# STEVAL-ESLST25CB.net
KiCad netlist of a schematic drawn in Altium Designer
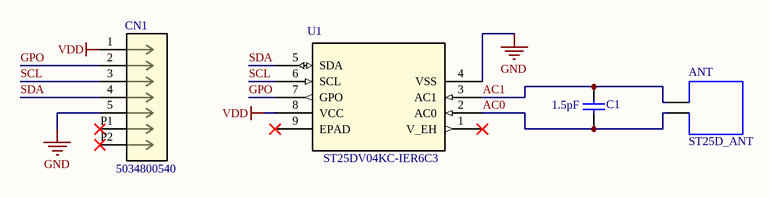
[diagram p0: STEVAL-ESLST25CB.SchDoc]

(export (version "E")
  (design (tool "Eeschema 10.0.6"))
  (components
    (comp (ref "ANT")
      (value "ST25D_ANT")
      (footprint "ESL_NFC_ANT")
      (description "ST25D antenna")
      (libsource (lib "STEVAL-ESLST25CB") (part "ST25D_ANT"))
    )
    (comp (ref "C1")
      (value "1.5pF")
      (footprint "C0402")
      (description "Multilayer Ceramic Capacitor, 1.5 pF, 50 V, ± 0.1pF, C0G (NP0), 0402 [1005 Metric]")
      (fields
        (field (name "MANUFACTURER") "Murata")
        (field (name "MANUFACTURER PART NUMBER") "GJM1555C1H1R5BB01D")
      )
      (libsource (lib "STEVAL-ESLST25CB") (part "Capacitor"))
    )
    (comp (ref "CN1")
      (value "5034800540")
      (footprint "CON_5034800540_MOL")
      (fields
        (field (name "MANUFACTURER") "Molex Connector Corporation")
        (field (name "COPYRIGHT") "Copyright (C) 2023 Ultra Librarian. All rights reserved.")
      )
      (libsource (lib "STEVAL-ESLST25CB") (part "5034800540_5_circuits"))
    )
    (comp (ref "U1")
      (value "ST25DV04KC-IER6C3")
      (footprint "UFDFPN8_STM")
      (description "NFC/RFID Tag and Transponder IC 13553kHz to 13567kHz 4Kbit 8-Pin UFDFPN T/R")
      (fields
        (field (name "MANUFACTURER_PART_NUMBER") "ST25DV04K-IER6C3")
        (field (name "MANUFACTURER") "STMicroelectronics")
        (field (name "COPYRIGHT") "Copyright (C) 2023 Ultra Librarian. All rights reserved.")
      )
      (libsource (lib "STEVAL-ESLST25CB") (part "ST25DV04K-IER6C3"))
    )
  )
  (nets
    (net (code "1") (name "/AC0") (class "Default")
      (node (ref "ANT") (pin "2") (pinfunction "2_2") (pintype "passive"))
      (node (ref "C1") (pin "2") (pinfunction "2_2") (pintype "passive"))
      (node (ref "U1") (pin "2") (pinfunction "AC0_2") (pintype "input"))
    )
    (net (code "2") (name "/AC1") (class "Default")
      (node (ref "ANT") (pin "1") (pinfunction "1_1") (pintype "passive"))
      (node (ref "C1") (pin "1") (pinfunction "1_1") (pintype "passive"))
      (node (ref "U1") (pin "3") (pinfunction "AC1_3") (pintype "input"))
    )
    (net (code "3") (name "/GPO") (class "Default")
      (node (ref "CN1") (pin "2") (pinfunction "2_2") (pintype "passive"))
      (node (ref "U1") (pin "7") (pinfunction "GPO_7") (pintype "output"))
    )
    (net (code "4") (name "/SCL") (class "Default")
      (node (ref "CN1") (pin "3") (pinfunction "3_3") (pintype "passive"))
      (node (ref "U1") (pin "6") (pinfunction "SCL_6") (pintype "input"))
    )
    (net (code "5") (name "/SDA") (class "Default")
      (node (ref "CN1") (pin "4") (pinfunction "4_4") (pintype "passive"))
      (node (ref "U1") (pin "5") (pinfunction "SDA_5") (pintype "bidirectional"))
    )
    (net (code "6") (name "GND") (class "Default")
      (node (ref "CN1") (pin "5") (pinfunction "5_5") (pintype "passive"))
      (node (ref "U1") (pin "4") (pinfunction "VSS_4") (pintype "power_in"))
    )
    (net (code "7") (name "VDD") (class "Default")
      (node (ref "CN1") (pin "1") (pinfunction "1_1") (pintype "passive"))
      (node (ref "U1") (pin "8") (pinfunction "VCC_8") (pintype "power_in"))
    )
    (net (code "8") (name "unconnected-(CN1-PadP1)") (class "Default")
      (node (ref "CN1") (pin "P1") (pinfunction "P1_P1") (pintype "passive+no_connect"))
    )
    (net (code "9") (name "unconnected-(CN1-PadP2)") (class "Default")
      (node (ref "CN1") (pin "P2") (pinfunction "P2_P2") (pintype "passive+no_connect"))
    )
    (net (code "10") (name "unconnected-(U1-EPAD-Pad9)") (class "Default")
      (node (ref "U1") (pin "9") (pinfunction "EPAD_9") (pintype "power_in+no_connect"))
    )
    (net (code "11") (name "unconnected-(U1-V_EH-Pad1)") (class "Default")
      (node (ref "U1") (pin "1") (pinfunction "V_EH_1") (pintype "output+no_connect"))
    )
  )
)
